# Oscillator_RevA.net
KiCad netlist of a schematic drawn in EAGLE
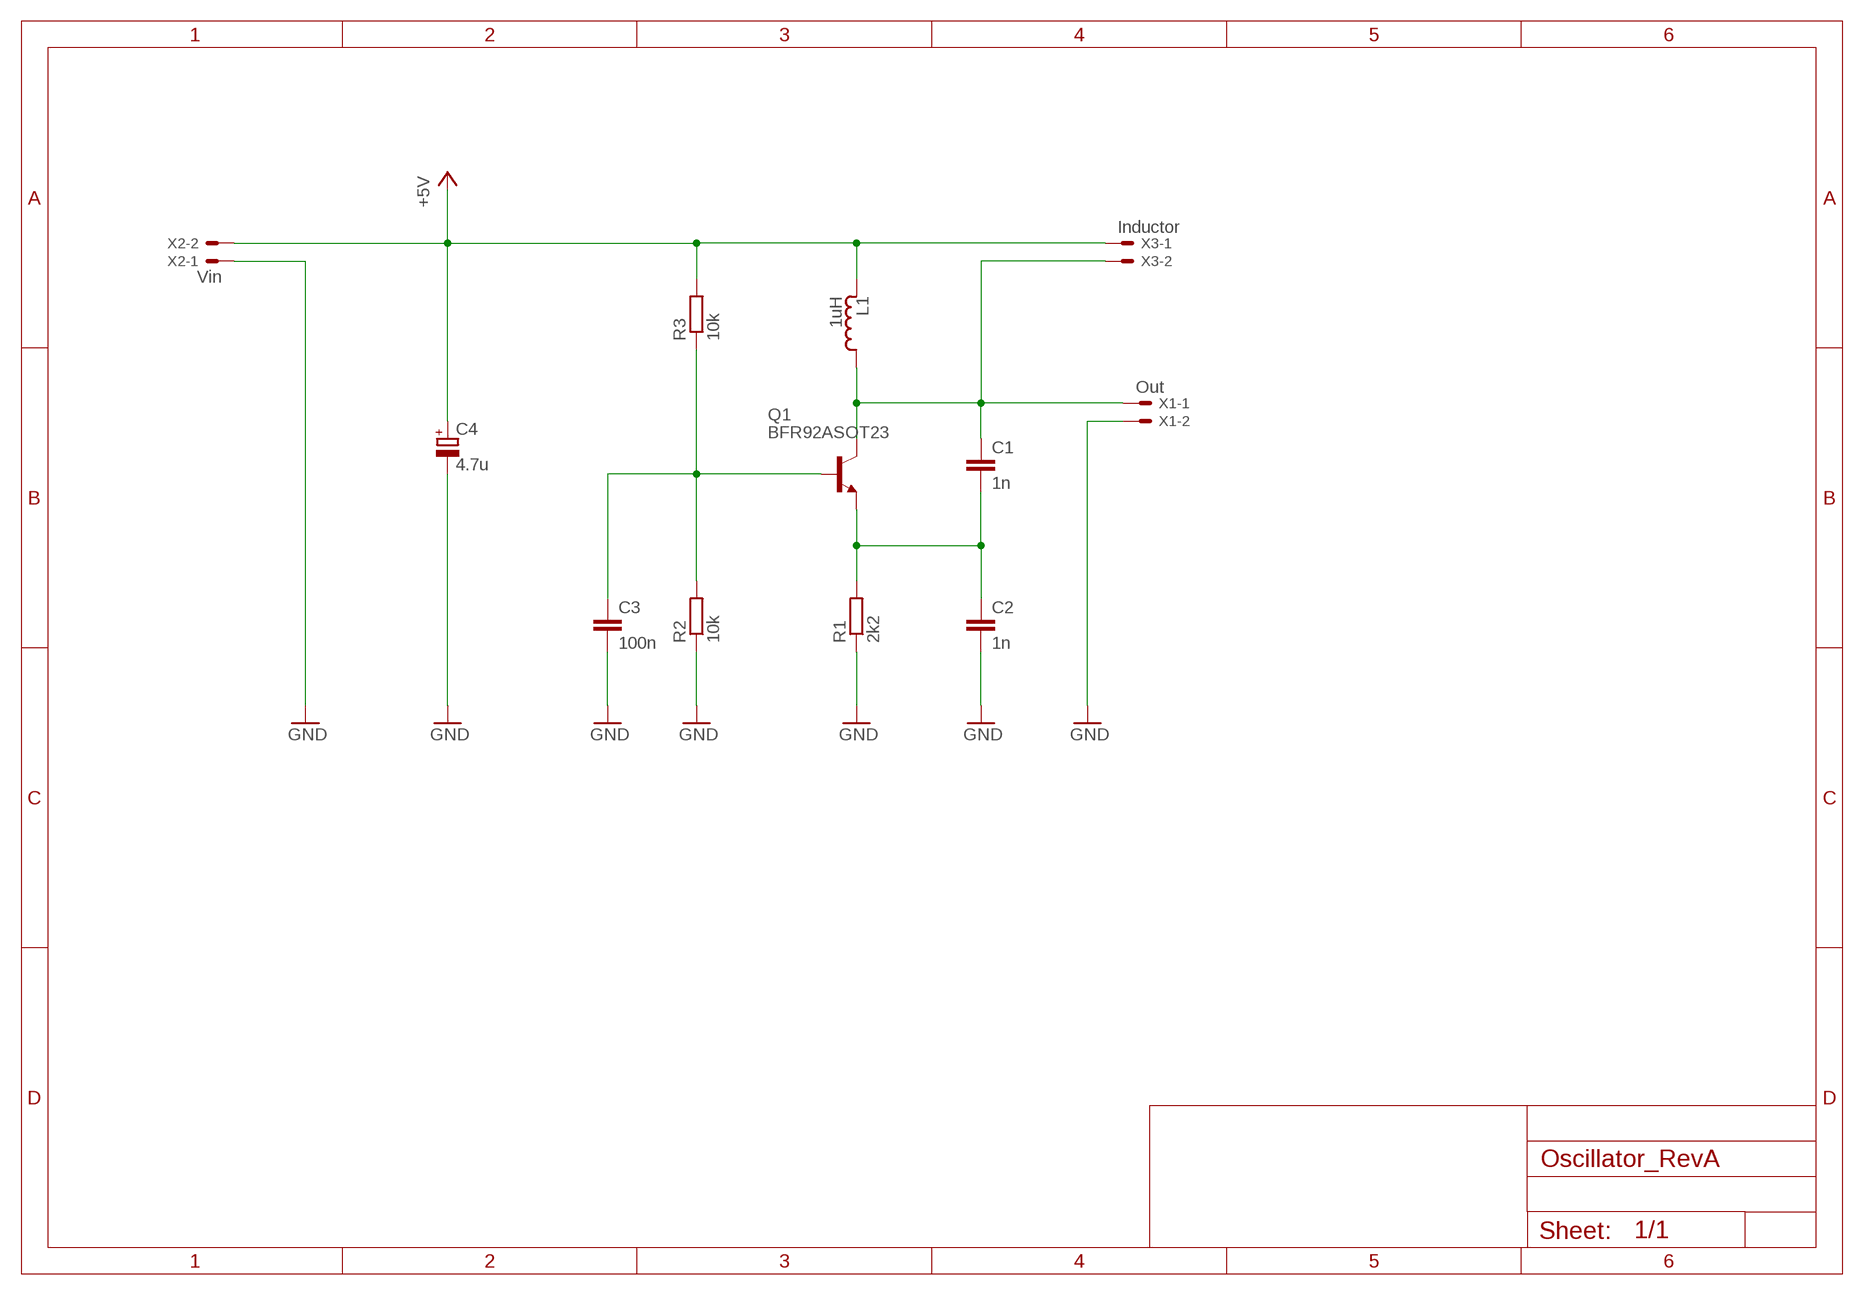
[diagram p0: schematic, sheet 1]

(export (version "E")
  (design (tool "Eeschema 10.0.6"))
  (components
    (comp (ref "C1")
      (value "1n")
      (footprint "eagle-import:C0805")
      (libsource (lib "eagle-import") (part "CC0805"))
    )
    (comp (ref "C2")
      (value "1n")
      (footprint "eagle-import:C0805")
      (libsource (lib "eagle-import") (part "CC0805"))
    )
    (comp (ref "C3")
      (value "100n")
      (footprint "eagle-import:C0805")
      (libsource (lib "eagle-import") (part "CC0805"))
    )
    (comp (ref "C4")
      (value "4.7u")
      (footprint "eagle-import:SMC_C")
      (libsource (lib "eagle-import") (part "C_POLARIZEDSMC_C"))
    )
    (comp (ref "L1")
      (value "1uH")
      (footprint "eagle-import:LPS4414")
      (libsource (lib "eagle-import") (part "INDUCTOR4.3MM"))
    )
    (comp (ref "Q1")
      (value "BFR92ASOT23")
      (footprint "eagle-import:SOT23")
      (libsource (lib "eagle-import") (part "BFR92ASOT23"))
    )
    (comp (ref "R1")
      (value "2k2")
      (footprint "eagle-import:R0805")
      (libsource (lib "eagle-import") (part "RESISTORR0805"))
    )
    (comp (ref "R2")
      (value "10k")
      (footprint "eagle-import:R0805")
      (libsource (lib "eagle-import") (part "RESISTORR0805"))
    )
    (comp (ref "R3")
      (value "10k")
      (footprint "eagle-import:R0805")
      (libsource (lib "eagle-import") (part "RESISTORR0805"))
    )
    (comp (ref "X1")
      (value "Out")
      (footprint "eagle-import:22-23-2021")
      (fields (field (name "MF") "MOLEX") (field (name "MPN") "22-23-2021"))
      (libsource (lib "eagle-import") (part "22-23-2021100MIL"))
    )
    (comp (ref "X2")
      (value "Vin")
      (footprint "eagle-import:22-23-2021")
      (fields (field (name "MF") "MOLEX") (field (name "MPN") "22-23-2021"))
      (libsource (lib "eagle-import") (part "22-23-2021100MIL"))
    )
    (comp (ref "X3")
      (value "Inductor")
      (footprint "eagle-import:22-23-2021")
      (fields (field (name "MF") "MOLEX") (field (name "MPN") "22-23-2021"))
      (libsource (lib "eagle-import") (part "22-23-2021100MIL"))
    )
  )
  (nets
    (net (code "1") (name "+5V") (class "Default")
      (node (ref "C4") (pin "+") (pinfunction "+_+") (pintype "passive"))
      (node (ref "L1") (pin "2") (pinfunction "2_2") (pintype "passive"))
      (node (ref "R3") (pin "2") (pinfunction "2_2") (pintype "passive"))
      (node (ref "X2") (pin "2") (pinfunction "S_2") (pintype "passive"))
      (node (ref "X3") (pin "1") (pinfunction "S_1") (pintype "passive"))
    )
    (net (code "2") (name "GND") (class "Default")
      (node (ref "C2") (pin "2") (pinfunction "2_2") (pintype "passive"))
      (node (ref "C3") (pin "2") (pinfunction "2_2") (pintype "passive"))
      (node (ref "C4") (pin "-") (pinfunction "-_-") (pintype "passive"))
      (node (ref "R1") (pin "1") (pinfunction "1_1") (pintype "passive"))
      (node (ref "R2") (pin "1") (pinfunction "1_1") (pintype "passive"))
      (node (ref "X1") (pin "2") (pinfunction "S_2") (pintype "passive"))
      (node (ref "X2") (pin "1") (pinfunction "S_1") (pintype "passive"))
    )
    (net (code "3") (name "Net-(Q1-B)") (class "Default")
      (node (ref "C3") (pin "1") (pinfunction "1_1") (pintype "passive"))
      (node (ref "Q1") (pin "1") (pinfunction "B_1") (pintype "passive"))
      (node (ref "R2") (pin "2") (pinfunction "2_2") (pintype "passive"))
      (node (ref "R3") (pin "1") (pinfunction "1_1") (pintype "passive"))
    )
    (net (code "4") (name "Net-(Q1-C)") (class "Default")
      (node (ref "C1") (pin "1") (pinfunction "1_1") (pintype "passive"))
      (node (ref "L1") (pin "1") (pinfunction "1_1") (pintype "passive"))
      (node (ref "Q1") (pin "3") (pinfunction "C_3") (pintype "passive"))
      (node (ref "X1") (pin "1") (pinfunction "S_1") (pintype "passive"))
      (node (ref "X3") (pin "2") (pinfunction "S_2") (pintype "passive"))
    )
    (net (code "5") (name "Net-(Q1-E)") (class "Default")
      (node (ref "C1") (pin "2") (pinfunction "2_2") (pintype "passive"))
      (node (ref "C2") (pin "1") (pinfunction "1_1") (pintype "passive"))
      (node (ref "Q1") (pin "2") (pinfunction "E_2") (pintype "passive"))
      (node (ref "R1") (pin "2") (pinfunction "2_2") (pintype "passive"))
    )
  )
)
